# design.net
KiCad netlist of a schematic drawn in EasyEDA Pro
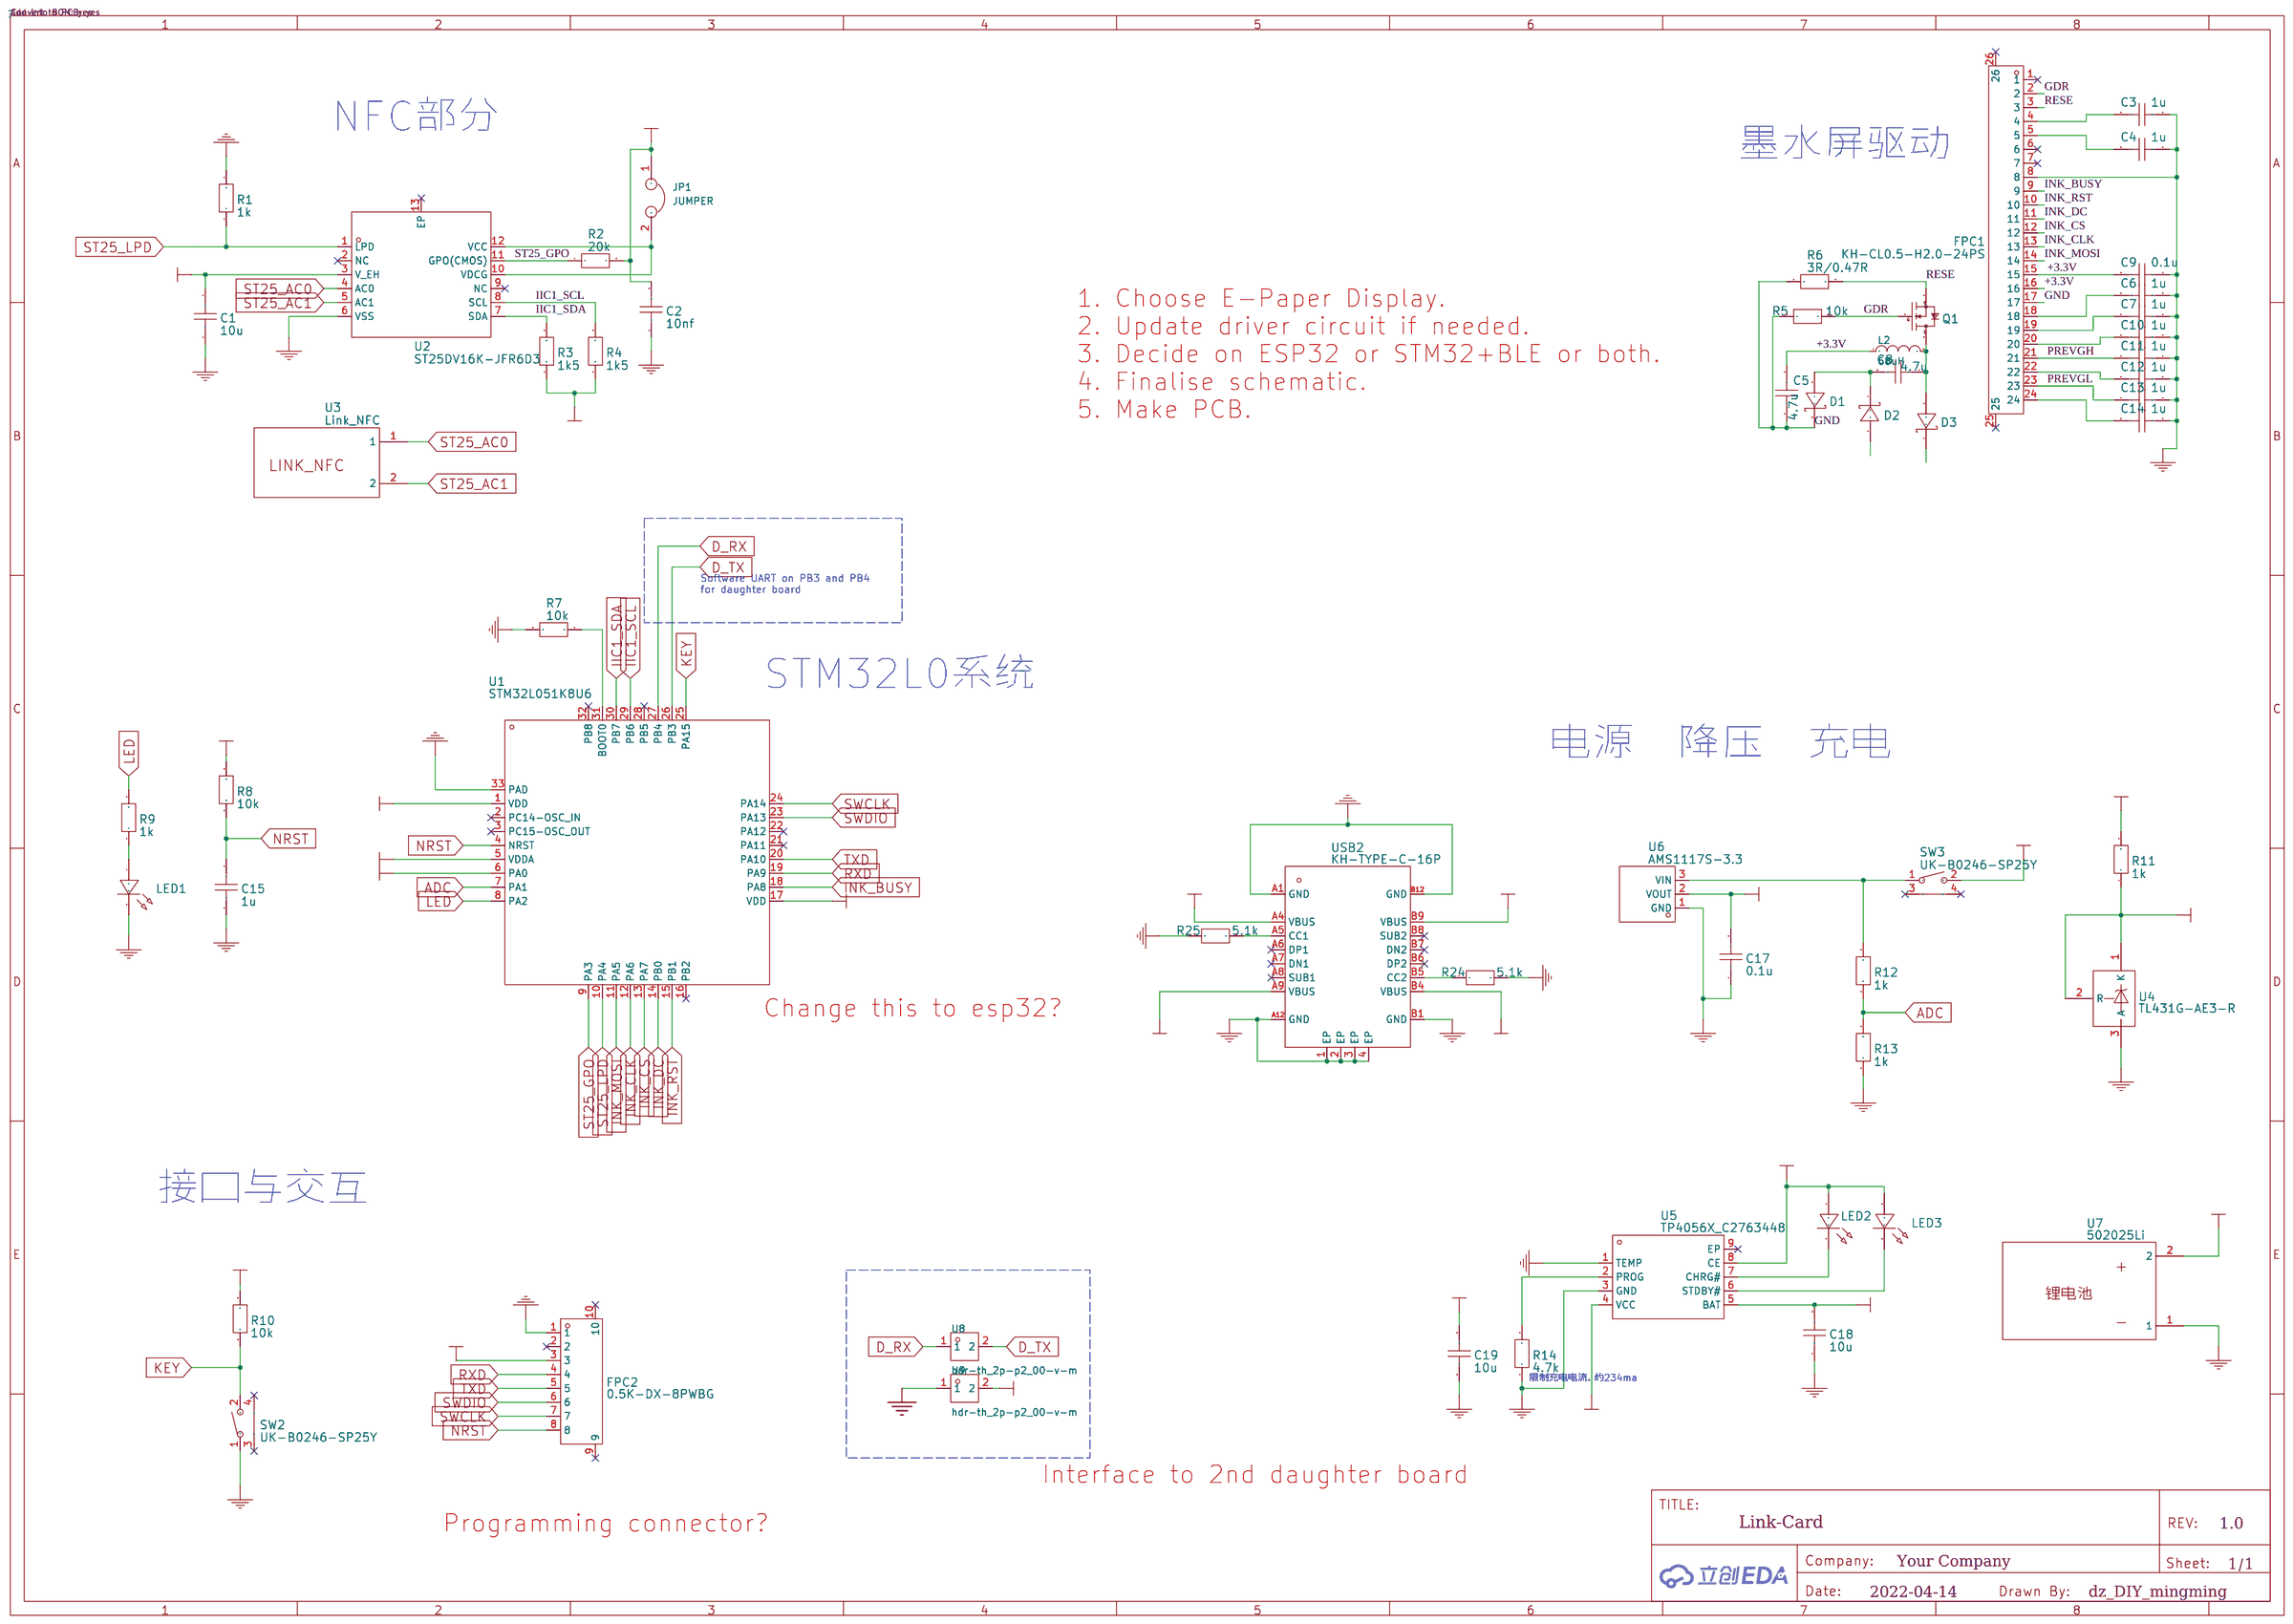
[diagram p0: schematic sheet]

(export (version "E")
  (design (tool "Eeschema 10.0.6"))
  (components
    (comp (ref "C1") (value "10u") (footprint "easyedapro:C0805") (libsource (lib "easyedapro") (part "10u")))
    (comp (ref "C2")
      (value "10nf")
      (footprint "easyedapro:C0603")
      (libsource (lib "easyedapro") (part "10nf"))
    )
    (comp (ref "C3") (value "1u") (footprint "easyedapro:C0603") (libsource (lib "easyedapro") (part "1u")))
    (comp (ref "C4") (value "1u") (footprint "easyedapro:C0603") (libsource (lib "easyedapro") (part "1u")))
    (comp (ref "C5")
      (value "4.7u")
      (footprint "easyedapro:C0603")
      (libsource (lib "easyedapro") (part "4.7u"))
    )
    (comp (ref "C6") (value "1u") (footprint "easyedapro:C0603") (libsource (lib "easyedapro") (part "1u")))
    (comp (ref "C7") (value "1u") (footprint "easyedapro:C0603") (libsource (lib "easyedapro") (part "1u")))
    (comp (ref "C8")
      (value "4.7u")
      (footprint "easyedapro:C0603")
      (libsource (lib "easyedapro") (part "4.7u"))
    )
    (comp (ref "C9")
      (value "0.1u")
      (footprint "easyedapro:C0603")
      (libsource (lib "easyedapro") (part "0.1u"))
    )
    (comp (ref "C10") (value "1u") (footprint "easyedapro:C0603") (libsource (lib "easyedapro") (part "1u")))
    (comp (ref "C11") (value "1u") (footprint "easyedapro:C0603") (libsource (lib "easyedapro") (part "1u")))
    (comp (ref "C12") (value "1u") (footprint "easyedapro:C0603") (libsource (lib "easyedapro") (part "1u")))
    (comp (ref "C13") (value "1u") (footprint "easyedapro:C0603") (libsource (lib "easyedapro") (part "1u")))
    (comp (ref "C14") (value "1u") (footprint "easyedapro:C0603") (libsource (lib "easyedapro") (part "1u")))
    (comp (ref "C15") (value "1u") (footprint "easyedapro:C0603") (libsource (lib "easyedapro") (part "1u")))
    (comp (ref "C17")
      (value "0.1u")
      (footprint "easyedapro:C0603")
      (libsource (lib "easyedapro") (part "0.1u"))
    )
    (comp (ref "C18")
      (value "10u")
      (footprint "easyedapro:C0805")
      (libsource (lib "easyedapro") (part "10u"))
    )
    (comp (ref "C19")
      (value "10u")
      (footprint "easyedapro:C0805")
      (libsource (lib "easyedapro") (part "10u"))
    )
    (comp (ref "D1")
      (value "MBR0530")
      (footprint "easyedapro:SOD-123F_L2.7-W1.7-LS3.7-RD-1")
      (libsource (lib "easyedapro") (part "MBR0530"))
    )
    (comp (ref "D2")
      (value "MBR0530")
      (footprint "easyedapro:SOD-123F_L2.7-W1.7-LS3.7-RD-1")
      (libsource (lib "easyedapro") (part "MBR0530"))
    )
    (comp (ref "D3")
      (value "MBR0530")
      (footprint "easyedapro:SOD-123F_L2.7-W1.7-LS3.7-RD-1")
      (libsource (lib "easyedapro") (part "MBR0530"))
    )
    (comp (ref "FPC1")
      (value "KH-CL0.5-H2.0-24PS")
      (footprint "easyedapro:FPC-SMD_24P-P0.50_KINGHELM_KH-CL0.5-H2.0-24PS")
      (fields (field (name "Manufacturer") "kinghelm(金航标)"))
      (libsource (lib "easyedapro") (part "KH-CL0.5-H2.0-24PS"))
    )
    (comp (ref "FPC2")
      (value "0.5K-DX-8PWBG")
      (footprint "easyedapro:FPC-SMD_8P-P0.50_HDGC_0.5K-DX-8PWBG")
      (fields (field (name "Manufacturer") "HDGC(华德共创)"))
      (libsource (lib "easyedapro") (part "0.5K-DX-8PWBG"))
    )
    (comp (ref "JP1")
      (value "JUMPER")
      (footprint "easyedapro:JUMPER-0603")
      (libsource (lib "easyedapro") (part "JUMPER"))
    )
    (comp (ref "L2")
      (value "68uH")
      (footprint "easyedapro:IND-SMD_L5.8-W5.2")
      (description "电感值:68uH;精度:±10%;额定电流:600mA;饱和电流(Isat):-;直流电阻(DCR):390mΩ;")
      (fields (field (name "Manufacturer Part") "CY54-68UH") (field (name "Manufacturer") "SHOU HAN(首韩)"))
      (libsource (lib "easyedapro") (part "CY54-68UH"))
    )
    (comp (ref "LED1")
      (value "LED-0805_B")
      (footprint "easyedapro:LED0805_BLUE")
      (fields (field (name "Manufacturer Part") "D-B080508B1-KS2") (field (name "Manufacturer") "方舟 ARKLED"))
      (libsource (lib "easyedapro") (part "LED-0805_B"))
    )
    (comp (ref "LED2")
      (value "LED-0805_R")
      (footprint "easyedapro:LED0805_RED")
      (fields
        (field (name "Manufacturer Part") "17-21SURC/S530-A3/TR8")
        (field (name "Manufacturer") "EVERLIGHT(台湾亿光)")
      )
      (libsource (lib "easyedapro") (part "LED-0805_R"))
    )
    (comp (ref "LED3")
      (value "LED-0805_G")
      (footprint "easyedapro:LED0805_GREEN")
      (fields (field (name "Manufacturer Part") "NCD0805G1") (field (name "Manufacturer") "国星光电"))
      (libsource (lib "easyedapro") (part "LED-0805_G"))
    )
    (comp (ref "Q1")
      (value "MOSFET-N+SI1304BDL")
      (footprint "easyedapro:SOT-323-3_L2.0-W1.3-P1.30-LS2.1-BR")
      (fields (field (name "Manufacturer Part") "?"))
      (libsource (lib "easyedapro") (part "MOSFET-N+SI1304BDL"))
    )
    (comp (ref "R1") (value "1k") (footprint "easyedapro:R0603") (libsource (lib "easyedapro") (part "1k")))
    (comp (ref "R2") (value "20k") (footprint "easyedapro:R0603") (libsource (lib "easyedapro") (part "20k")))
    (comp (ref "R3") (value "1k5") (footprint "easyedapro:R0603") (libsource (lib "easyedapro") (part "1k5")))
    (comp (ref "R4") (value "1k5") (footprint "easyedapro:R0603") (libsource (lib "easyedapro") (part "1k5")))
    (comp (ref "R5") (value "10k") (footprint "easyedapro:R0603") (libsource (lib "easyedapro") (part "10k")))
    (comp (ref "R6")
      (value "3R/0.47R")
      (footprint "easyedapro:R0603")
      (libsource (lib "easyedapro") (part "3R/0.47R"))
    )
    (comp (ref "R7") (value "10k") (footprint "easyedapro:R0603") (libsource (lib "easyedapro") (part "10k")))
    (comp (ref "R8") (value "10k") (footprint "easyedapro:R0603") (libsource (lib "easyedapro") (part "10k")))
    (comp (ref "R9") (value "1k") (footprint "easyedapro:R0603") (libsource (lib "easyedapro") (part "1k")))
    (comp (ref "R10")
      (value "10k")
      (footprint "easyedapro:R0603")
      (libsource (lib "easyedapro") (part "10k"))
    )
    (comp (ref "R11") (value "1k") (footprint "easyedapro:R0603") (libsource (lib "easyedapro") (part "1k")))
    (comp (ref "R12") (value "1k") (footprint "easyedapro:R0603") (libsource (lib "easyedapro") (part "1k")))
    (comp (ref "R13") (value "1k") (footprint "easyedapro:R0603") (libsource (lib "easyedapro") (part "1k")))
    (comp (ref "R14")
      (value "4.7k")
      (footprint "easyedapro:R0603")
      (libsource (lib "easyedapro") (part "4.7k"))
    )
    (comp (ref "R24")
      (value "5.1k")
      (footprint "easyedapro:R0603")
      (libsource (lib "easyedapro") (part "5.1k"))
    )
    (comp (ref "R25")
      (value "5.1k")
      (footprint "easyedapro:R0603")
      (libsource (lib "easyedapro") (part "5.1k"))
    )
    (comp (ref "SW2")
      (value "UK-B0246-SP25Y")
      (footprint "easyedapro:SW-SMD_UK-B0246-SP25Y")
      (fields (field (name "Manufacturer") "USAKRO"))
      (libsource (lib "easyedapro") (part "UK-B0246-SP25Y"))
    )
    (comp (ref "SW3")
      (value "UK-B0246-SP25Y")
      (footprint "easyedapro:SW-SMD_UK-B0246-SP25Y")
      (fields (field (name "Manufacturer") "USAKRO"))
      (libsource (lib "easyedapro") (part "UK-B0246-SP25Y"))
    )
    (comp (ref "U1")
      (value "STM32L051K8U6")
      (footprint "easyedapro:UFQFPN-32_L5.0-W5.0-P0.50-BL-EP")
      (fields (field (name "Manufacturer") "STMicroelectronics"))
      (libsource (lib "easyedapro") (part "STM32L051K8U6"))
    )
    (comp (ref "U2")
      (value "ST25DV16K-JFR6D3")
      (footprint "easyedapro:DFN-12_L3.0-W3.0-P0.50-LS3.0-BL-EP")
      (libsource (lib "easyedapro") (part "ST25DV16K-JFR6D3"))
    )
    (comp (ref "U3")
      (value "Link_NFC")
      (footprint "easyedapro:LINK_NFC")
      (libsource (lib "easyedapro") (part "Link_NFC"))
    )
    (comp (ref "U4")
      (value "TL431G-AE3-R")
      (footprint "easyedapro:SOT-23-3_L2.9-W1.3-P1.90-LS2.4-TR")
      (fields (field (name "Manufacturer") "UTC"))
      (libsource (lib "easyedapro") (part "TL431G-AE3-R"))
    )
    (comp (ref "U5")
      (value "TP4056X_C2763448")
      (footprint "easyedapro:SOP-8_L4.9-W3.9-P1.27-LS6.0-TL-EP-1")
      (fields (field (name "Manufacturer Part") "TP4056X") (field (name "Manufacturer") "TOPPOWER(南京拓微)"))
      (libsource (lib "easyedapro") (part "TP4056X_C2763448"))
    )
    (comp (ref "U6")
      (value "AMS1117S-3.3")
      (footprint "easyedapro:SOT-89-3_L4.5-W2.5-P1.50-LS4.2-BR")
      (fields (field (name "Manufacturer") "JSMSEMI"))
      (libsource (lib "easyedapro") (part "AMS1117S-3.3"))
    )
    (comp (ref "U7")
      (value "502025Li")
      (footprint "easyedapro:502025LI")
      (libsource (lib "easyedapro") (part "502025Li"))
    )
    (comp (ref "U8")
      (value "hdr-th_2p-p2_00-v-m")
      (footprint "easyedapro:HDR-TH_2P-P2.00-V-M-1")
      (libsource (lib "easyedapro") (part "HDR-TH_2P-P2_00-V-M"))
    )
    (comp (ref "U9")
      (value "hdr-th_2p-p2_00-v-m")
      (footprint "easyedapro:HDR-TH_2P-P2.00-V-M-1")
      (libsource (lib "easyedapro") (part "HDR-TH_2P-P2_00-V-M"))
    )
    (comp (ref "USB2")
      (value "KH-TYPE-C-16P")
      (footprint "easyedapro:USB-C-SMD_KH-TYPE-C-16P")
      (fields (field (name "Manufacturer") "Shenzhen Kinghelm Elec"))
      (libsource (lib "easyedapro") (part "KH-TYPE-C-16P"))
    )
  )
  (nets
    (net (code "1") (name "+2.5V") (class "Default")
      (node (ref "R11") (pin "1") (pinfunction "1_1") (pintype "input"))
      (node (ref "U1") (pin "6") (pinfunction "PA0_6") (pintype "input"))
      (node (ref "U4") (pin "1") (pinfunction "K_1") (pintype "input"))
      (node (ref "U4") (pin "2") (pinfunction "R_2") (pintype "input"))
    )
    (net (code "2") (name "+3.3V") (class "Default")
      (node (ref "C1") (pin "2") (pinfunction "2_2") (pintype "input"))
      (node (ref "C17") (pin "2") (pinfunction "2_2") (pintype "input"))
      (node (ref "C2") (pin "2") (pinfunction "2_2") (pintype "input"))
      (node (ref "C5") (pin "2") (pinfunction "2_2") (pintype "input"))
      (node (ref "C9") (pin "1") (pinfunction "1_1") (pintype "input"))
      (node (ref "FPC1") (pin "15") (pinfunction "15_15") (pintype "input"))
      (node (ref "FPC1") (pin "16") (pinfunction "16_16") (pintype "input"))
      (node (ref "FPC2") (pin "3") (pinfunction "3_3") (pintype "input"))
      (node (ref "JP1") (pin "1") (pinfunction "1_1") (pintype "input"))
      (node (ref "L2") (pin "1") (pinfunction "1_1") (pintype "input"))
      (node (ref "R10") (pin "2") (pinfunction "2_2") (pintype "input"))
      (node (ref "R11") (pin "2") (pinfunction "2_2") (pintype "input"))
      (node (ref "R2") (pin "2") (pinfunction "2_2") (pintype "input"))
      (node (ref "R3") (pin "1") (pinfunction "1_1") (pintype "input"))
      (node (ref "R4") (pin "1") (pinfunction "1_1") (pintype "input"))
      (node (ref "R8") (pin "2") (pinfunction "2_2") (pintype "input"))
      (node (ref "U1") (pin "1") (pinfunction "VDD_1") (pintype "input"))
      (node (ref "U1") (pin "17") (pinfunction "VDD_17") (pintype "input"))
      (node (ref "U1") (pin "5") (pinfunction "VDDA_5") (pintype "input"))
      (node (ref "U2") (pin "3") (pinfunction "V_EH_3") (pintype "input"))
      (node (ref "U6") (pin "2") (pinfunction "VOUT_2") (pintype "input"))
    )
    (net (code "3") (name "+5V") (class "Default")
      (node (ref "C19") (pin "2") (pinfunction "2_2") (pintype "input"))
      (node (ref "LED2") (pin "1") (pinfunction "1_1") (pintype "input"))
      (node (ref "LED3") (pin "1") (pinfunction "1_1") (pintype "input"))
      (node (ref "U5") (pin "4") (pinfunction "VCC_4") (pintype "input"))
      (node (ref "U5") (pin "8") (pinfunction "CE_8") (pintype "input"))
      (node (ref "USB2") (pin "A4") (pinfunction "VBUS_A4") (pintype "input"))
      (node (ref "USB2") (pin "A9") (pinfunction "VBUS_A9") (pintype "input"))
      (node (ref "USB2") (pin "B4") (pinfunction "VBUS_B4") (pintype "input"))
      (node (ref "USB2") (pin "B9") (pinfunction "VBUS_B9") (pintype "input"))
    )
    (net (code "4") (name "/GDR") (class "Default")
      (node (ref "FPC1") (pin "2") (pinfunction "2_2") (pintype "input"))
      (node (ref "Q1") (pin "1") (pinfunction "G_1") (pintype "input"))
      (node (ref "R5") (pin "2") (pinfunction "2_2") (pintype "input"))
    )
    (net (code "5") (name "/PREVGH") (class "Default")
      (node (ref "C11") (pin "1") (pinfunction "1_1") (pintype "input"))
      (node (ref "FPC1") (pin "21") (pinfunction "21_21") (pintype "input"))
    )
    (net (code "6") (name "/PREVGL") (class "Default")
      (node (ref "C13") (pin "1") (pinfunction "1_1") (pintype "input"))
      (node (ref "FPC1") (pin "23") (pinfunction "23_23") (pintype "input"))
    )
    (net (code "7") (name "/RESE") (class "Default")
      (node (ref "FPC1") (pin "3") (pinfunction "3_3") (pintype "input"))
      (node (ref "Q1") (pin "2") (pinfunction "S_2") (pintype "input"))
      (node (ref "R6") (pin "2") (pinfunction "2_2") (pintype "input"))
    )
    (net (code "8") (name "ADC") (class "Default")
      (node (ref "R12") (pin "1") (pinfunction "1_1") (pintype "input"))
      (node (ref "R13") (pin "2") (pinfunction "2_2") (pintype "input"))
      (node (ref "U1") (pin "7") (pinfunction "PA1_7") (pintype "input"))
    )
    (net (code "9") (name "D_RX") (class "Default")
      (node (ref "U1") (pin "27") (pinfunction "PB4_27") (pintype "input"))
      (node (ref "U8") (pin "1") (pinfunction "1_1") (pintype "input"))
    )
    (net (code "10") (name "D_TX") (class "Default")
      (node (ref "U1") (pin "26") (pinfunction "PB3_26") (pintype "input"))
      (node (ref "U8") (pin "2") (pinfunction "2_2") (pintype "input"))
    )
    (net (code "11") (name "GND") (class "Default")
      (node (ref "C1") (pin "1") (pinfunction "1_1") (pintype "input"))
      (node (ref "C10") (pin "2") (pinfunction "2_2") (pintype "input"))
      (node (ref "C11") (pin "2") (pinfunction "2_2") (pintype "input"))
      (node (ref "C12") (pin "2") (pinfunction "2_2") (pintype "input"))
      (node (ref "C13") (pin "2") (pinfunction "2_2") (pintype "input"))
      (node (ref "C14") (pin "2") (pinfunction "2_2") (pintype "input"))
      (node (ref "C15") (pin "1") (pinfunction "1_1") (pintype "input"))
      (node (ref "C17") (pin "1") (pinfunction "1_1") (pintype "input"))
      (node (ref "C18") (pin "1") (pinfunction "1_1") (pintype "input"))
      (node (ref "C19") (pin "1") (pinfunction "1_1") (pintype "input"))
      (node (ref "C2") (pin "1") (pinfunction "1_1") (pintype "input"))
      (node (ref "C3") (pin "2") (pinfunction "2_2") (pintype "input"))
      (node (ref "C4") (pin "2") (pinfunction "2_2") (pintype "input"))
      (node (ref "C5") (pin "1") (pinfunction "1_1") (pintype "input"))
      (node (ref "C6") (pin "2") (pinfunction "2_2") (pintype "input"))
      (node (ref "C7") (pin "2") (pinfunction "2_2") (pintype "input"))
      (node (ref "C9") (pin "2") (pinfunction "2_2") (pintype "input"))
      (node (ref "D1") (pin "1") (pinfunction "K_1") (pintype "input"))
      (node (ref "FPC1") (pin "17") (pinfunction "17_17") (pintype "input"))
      (node (ref "FPC1") (pin "8") (pinfunction "8_8") (pintype "input"))
      (node (ref "FPC2") (pin "1") (pinfunction "1_1") (pintype "input"))
      (node (ref "LED1") (pin "2") (pinfunction "2_2") (pintype "input"))
      (node (ref "R1") (pin "2") (pinfunction "2_2") (pintype "input"))
      (node (ref "R13") (pin "1") (pinfunction "1_1") (pintype "input"))
      (node (ref "R14") (pin "1") (pinfunction "1_1") (pintype "input"))
      (node (ref "R24") (pin "2") (pinfunction "2_2") (pintype "input"))
      (node (ref "R25") (pin "1") (pinfunction "1_1") (pintype "input"))
      (node (ref "R5") (pin "1") (pinfunction "1_1") (pintype "input"))
      (node (ref "R6") (pin "1") (pinfunction "1_1") (pintype "input"))
      (node (ref "R7") (pin "2") (pinfunction "2_2") (pintype "input"))
      (node (ref "SW2") (pin "1") (pinfunction "1_1") (pintype "input"))
      (node (ref "U1") (pin "33") (pinfunction "PAD_33") (pintype "input"))
      (node (ref "U2") (pin "6") (pinfunction "VSS_6") (pintype "input"))
      (node (ref "U4") (pin "3") (pinfunction "A_3") (pintype "input"))
      (node (ref "U5") (pin "1") (pinfunction "TEMP_1") (pintype "input"))
      (node (ref "U5") (pin "3") (pinfunction "GND_3") (pintype "input"))
      (node (ref "U6") (pin "1") (pinfunction "GND_1") (pintype "input"))
      (node (ref "U7") (pin "1") (pinfunction "1_1") (pintype "input"))
      (node (ref "U9") (pin "1") (pinfunction "1_1") (pintype "input"))
      (node (ref "USB2") (pin "1") (pinfunction "EP_1") (pintype "input"))
      (node (ref "USB2") (pin "2") (pinfunction "EP_2") (pintype "input"))
      (node (ref "USB2") (pin "3") (pinfunction "EP_3") (pintype "input"))
      (node (ref "USB2") (pin "4") (pinfunction "EP_4") (pintype "input"))
      (node (ref "USB2") (pin "A1") (pinfunction "GND_A1") (pintype "input"))
      (node (ref "USB2") (pin "A12") (pinfunction "GND_A12") (pintype "input"))
      (node (ref "USB2") (pin "B1") (pinfunction "GND_B1") (pintype "input"))
      (node (ref "USB2") (pin "B12") (pinfunction "GND_B12") (pintype "input"))
    )
    (net (code "12") (name "IIC1_SCL") (class "Default")
      (node (ref "R4") (pin "2") (pinfunction "2_2") (pintype "input"))
      (node (ref "U1") (pin "29") (pinfunction "PB6_29") (pintype "input"))
      (node (ref "U2") (pin "8") (pinfunction "SCL_8") (pintype "input"))
    )
    (net (code "13") (name "IIC1_SDA") (class "Default")
      (node (ref "R3") (pin "2") (pinfunction "2_2") (pintype "input"))
      (node (ref "U1") (pin "30") (pinfunction "PB7_30") (pintype "input"))
      (node (ref "U2") (pin "7") (pinfunction "SDA_7") (pintype "input"))
    )
    (net (code "14") (name "INK_BUSY") (class "Default")
      (node (ref "FPC1") (pin "9") (pinfunction "9_9") (pintype "input"))
      (node (ref "U1") (pin "18") (pinfunction "PA8_18") (pintype "input"))
    )
    (net (code "15") (name "INK_CLK") (class "Default")
      (node (ref "FPC1") (pin "13") (pinfunction "13_13") (pintype "input"))
      (node (ref "U1") (pin "12") (pinfunction "PA6_12") (pintype "input"))
    )
    (net (code "16") (name "INK_CS") (class "Default")
      (node (ref "FPC1") (pin "12") (pinfunction "12_12") (pintype "input"))
      (node (ref "U1") (pin "13") (pinfunction "PA7_13") (pintype "input"))
    )
    (net (code "17") (name "INK_DC") (class "Default")
      (node (ref "FPC1") (pin "11") (pinfunction "11_11") (pintype "input"))
      (node (ref "U1") (pin "14") (pinfunction "PB0_14") (pintype "input"))
    )
    (net (code "18") (name "INK_MOSI") (class "Default")
      (node (ref "FPC1") (pin "14") (pinfunction "14_14") (pintype "input"))
      (node (ref "U1") (pin "11") (pinfunction "PA5_11") (pintype "input"))
    )
    (net (code "19") (name "INK_RST") (class "Default")
      (node (ref "FPC1") (pin "10") (pinfunction "10_10") (pintype "input"))
      (node (ref "U1") (pin "15") (pinfunction "PB1_15") (pintype "input"))
    )
    (net (code "20") (name "KEY") (class "Default")
      (node (ref "R10") (pin "1") (pinfunction "1_1") (pintype "input"))
      (node (ref "SW2") (pin "2") (pinfunction "2_2") (pintype "input"))
      (node (ref "U1") (pin "25") (pinfunction "PA15_25") (pintype "input"))
    )
    (net (code "21") (name "LED") (class "Default")
      (node (ref "R9") (pin "2") (pinfunction "2_2") (pintype "input"))
      (node (ref "U1") (pin "8") (pinfunction "PA2_8") (pintype "input"))
    )
    (net (code "22") (name "NRST") (class "Default")
      (node (ref "C15") (pin "2") (pinfunction "2_2") (pintype "input"))
      (node (ref "FPC2") (pin "8") (pinfunction "8_8") (pintype "input"))
      (node (ref "R8") (pin "1") (pinfunction "1_1") (pintype "input"))
      (node (ref "U1") (pin "4") (pinfunction "NRST_4") (pintype "input"))
    )
    (net (code "23") (name "Net-(C3-Pad1)") (class "Default")
      (node (ref "C3") (pin "1") (pinfunction "1_1") (pintype "input"))
      (node (ref "FPC1") (pin "4") (pinfunction "4_4") (pintype "input"))
    )
    (net (code "24") (name "Net-(C4-Pad1)") (class "Default")
      (node (ref "C4") (pin "1") (pinfunction "1_1") (pintype "input"))
      (node (ref "FPC1") (pin "5") (pinfunction "5_5") (pintype "input"))
    )
    (net (code "25") (name "Net-(C6-Pad1)") (class "Default")
      (node (ref "C6") (pin "1") (pinfunction "1_1") (pintype "input"))
      (node (ref "FPC1") (pin "18") (pinfunction "18_18") (pintype "input"))
    )
    (net (code "26") (name "Net-(C7-Pad1)") (class "Default")
      (node (ref "C7") (pin "1") (pinfunction "1_1") (pintype "input"))
      (node (ref "FPC1") (pin "19") (pinfunction "19_19") (pintype "input"))
    )
    (net (code "27") (name "Net-(C10-Pad1)") (class "Default")
      (node (ref "C10") (pin "1") (pinfunction "1_1") (pintype "input"))
      (node (ref "FPC1") (pin "20") (pinfunction "20_20") (pintype "input"))
    )
    (net (code "28") (name "Net-(C12-Pad1)") (class "Default")
      (node (ref "C12") (pin "1") (pinfunction "1_1") (pintype "input"))
      (node (ref "FPC1") (pin "22") (pinfunction "22_22") (pintype "input"))
    )
    (net (code "29") (name "Net-(C14-Pad1)") (class "Default")
      (node (ref "C14") (pin "1") (pinfunction "1_1") (pintype "input"))
      (node (ref "FPC1") (pin "24") (pinfunction "24_24") (pintype "input"))
    )
    (net (code "30") (name "Net-(D1-A)") (class "Default")
      (node (ref "C8") (pin "2") (pinfunction "2_2") (pintype "input"))
      (node (ref "D1") (pin "2") (pinfunction "A_2") (pintype "input"))
      (node (ref "D2") (pin "1") (pinfunction "K_1") (pintype "input"))
    )
    (net (code "31") (name "Net-(D3-A)") (class "Default")
      (node (ref "C8") (pin "1") (pinfunction "1_1") (pintype "input"))
      (node (ref "D3") (pin "2") (pinfunction "A_2") (pintype "input"))
      (node (ref "L2") (pin "2") (pinfunction "2_2") (pintype "input"))
      (node (ref "Q1") (pin "3") (pinfunction "D_3") (pintype "input"))
    )
    (net (code "32") (name "Net-(LED1-Pad1)") (class "Default")
      (node (ref "LED1") (pin "1") (pinfunction "1_1") (pintype "input"))
      (node (ref "R9") (pin "1") (pinfunction "1_1") (pintype "input"))
    )
    (net (code "33") (name "Net-(U1-BOOT0)") (class "Default")
      (node (ref "R7") (pin "1") (pinfunction "1_1") (pintype "input"))
      (node (ref "U1") (pin "31") (pinfunction "BOOT0_31") (pintype "input"))
    )
    (net (code "34") (name "Net-(U2-VCC)") (class "Default")
      (node (ref "JP1") (pin "2") (pinfunction "2_2") (pintype "input"))
      (node (ref "U2") (pin "10") (pinfunction "VDCG_10") (pintype "input"))
      (node (ref "U2") (pin "12") (pinfunction "VCC_12") (pintype "input"))
    )
    (net (code "35") (name "Net-(U5-CHRG#)") (class "Default")
      (node (ref "LED2") (pin "2") (pinfunction "2_2") (pintype "input"))
      (node (ref "U5") (pin "7") (pinfunction "CHRG#_7") (pintype "input"))
    )
    (net (code "36") (name "Net-(U5-PROG)") (class "Default")
      (node (ref "R14") (pin "2") (pinfunction "2_2") (pintype "input"))
      (node (ref "U5") (pin "2") (pinfunction "PROG_2") (pintype "input"))
    )
    (net (code "37") (name "Net-(U5-STDBY#)") (class "Default")
      (node (ref "LED3") (pin "2") (pinfunction "2_2") (pintype "input"))
      (node (ref "U5") (pin "6") (pinfunction "STDBY#_6") (pintype "input"))
    )
    (net (code "38") (name "Net-(U6-VIN)") (class "Default")
      (node (ref "R12") (pin "2") (pinfunction "2_2") (pintype "input"))
      (node (ref "SW3") (pin "1") (pinfunction "1_1") (pintype "input"))
      (node (ref "U6") (pin "3") (pinfunction "VIN_3") (pintype "input"))
    )
    (net (code "39") (name "Net-(USB2-CC1)") (class "Default")
      (node (ref "R25") (pin "2") (pinfunction "2_2") (pintype "input"))
      (node (ref "USB2") (pin "A5") (pinfunction "CC1_A5") (pintype "input"))
    )
    (net (code "40") (name "Net-(USB2-CC2)") (class "Default")
      (node (ref "R24") (pin "1") (pinfunction "1_1") (pintype "input"))
      (node (ref "USB2") (pin "B5") (pinfunction "CC2_B5") (pintype "input"))
    )
    (net (code "41") (name "RXD") (class "Default")
      (node (ref "FPC2") (pin "4") (pinfunction "4_4") (pintype "input"))
      (node (ref "U1") (pin "19") (pinfunction "PA9_19") (pintype "input"))
    )
    (net (code "42") (name "ST25_AC0") (class "Default")
      (node (ref "U2") (pin "4") (pinfunction "AC0_4") (pintype "input"))
      (node (ref "U3") (pin "1") (pinfunction "1_1") (pintype "input"))
    )
    (net (code "43") (name "ST25_AC1") (class "Default")
      (node (ref "U2") (pin "5") (pinfunction "AC1_5") (pintype "input"))
      (node (ref "U3") (pin "2") (pinfunction "2_2") (pintype "input"))
    )
    (net (code "44") (name "ST25_GPO") (class "Default")
      (node (ref "R2") (pin "1") (pinfunction "1_1") (pintype "input"))
      (node (ref "U1") (pin "9") (pinfunction "PA3_9") (pintype "input"))
      (node (ref "U2") (pin "11") (pinfunction "GPO(CMOS)_11") (pintype "input"))
    )
    (net (code "45") (name "ST25_LPD") (class "Default")
      (node (ref "R1") (pin "1") (pinfunction "1_1") (pintype "input"))
      (node (ref "U1") (pin "10") (pinfunction "PA4_10") (pintype "input"))
      (node (ref "U2") (pin "1") (pinfunction "LPD_1") (pintype "input"))
    )
    (net (code "46") (name "SWCLK") (class "Default")
      (node (ref "FPC2") (pin "7") (pinfunction "7_7") (pintype "input"))
      (node (ref "U1") (pin "24") (pinfunction "PA14_24") (pintype "input"))
    )
    (net (code "47") (name "SWDIO") (class "Default")
      (node (ref "FPC2") (pin "6") (pinfunction "6_6") (pintype "input"))
      (node (ref "U1") (pin "23") (pinfunction "PA13_23") (pintype "input"))
    )
    (net (code "48") (name "TXD") (class "Default")
      (node (ref "FPC2") (pin "5") (pinfunction "5_5") (pintype "input"))
      (node (ref "U1") (pin "20") (pinfunction "PA10_20") (pintype "input"))
    )
    (net (code "49") (name "VBAT") (class "Default")
      (node (ref "C18") (pin "2") (pinfunction "2_2") (pintype "input"))
      (node (ref "SW3") (pin "2") (pinfunction "2_2") (pintype "input"))
      (node (ref "U5") (pin "5") (pinfunction "BAT_5") (pintype "input"))
      (node (ref "U7") (pin "2") (pinfunction "2_2") (pintype "input"))
      (node (ref "U9") (pin "2") (pinfunction "2_2") (pintype "input"))
    )
    (net (code "50") (name "unconnected-(D2-A-Pad2)") (class "Default")
      (node (ref "D2") (pin "2") (pinfunction "A_2") (pintype "input"))
    )
    (net (code "51") (name "unconnected-(D3-K-Pad1)") (class "Default")
      (node (ref "D3") (pin "1") (pinfunction "K_1") (pintype "input"))
    )
    (net (code "52") (name "unconnected-(FPC1-Pad1)") (class "Default")
      (node (ref "FPC1") (pin "1") (pinfunction "1_1") (pintype "input+no_connect"))
    )
    (net (code "53") (name "unconnected-(FPC1-Pad6)") (class "Default")
      (node (ref "FPC1") (pin "6") (pinfunction "6_6") (pintype "input+no_connect"))
    )
    (net (code "54") (name "unconnected-(FPC1-Pad7)") (class "Default")
      (node (ref "FPC1") (pin "7") (pinfunction "7_7") (pintype "input+no_connect"))
    )
    (net (code "55") (name "unconnected-(FPC1-Pad25)") (class "Default")
      (node (ref "FPC1") (pin "25") (pinfunction "25_25") (pintype "input+no_connect"))
    )
    (net (code "56") (name "unconnected-(FPC1-Pad26)") (class "Default")
      (node (ref "FPC1") (pin "26") (pinfunction "26_26") (pintype "input+no_connect"))
    )
    (net (code "57") (name "unconnected-(FPC2-Pad2)") (class "Default")
      (node (ref "FPC2") (pin "2") (pinfunction "2_2") (pintype "input+no_connect"))
    )
    (net (code "58") (name "unconnected-(FPC2-Pad9)") (class "Default")
      (node (ref "FPC2") (pin "9") (pinfunction "9_9") (pintype "input+no_connect"))
    )
    (net (code "59") (name "unconnected-(FPC2-Pad10)") (class "Default")
      (node (ref "FPC2") (pin "10") (pinfunction "10_10") (pintype "input+no_connect"))
    )
    (net (code "60") (name "unconnected-(SW2-EP-Pad3)") (class "Default")
      (node (ref "SW2") (pin "3") (pinfunction "EP_3") (pintype "input+no_connect"))
    )
    (net (code "61") (name "unconnected-(SW2-EP-Pad4)") (class "Default")
      (node (ref "SW2") (pin "4") (pinfunction "EP_4") (pintype "input+no_connect"))
    )
    (net (code "62") (name "unconnected-(SW3-EP-Pad3)") (class "Default")
      (node (ref "SW3") (pin "3") (pinfunction "EP_3") (pintype "input+no_connect"))
    )
    (net (code "63") (name "unconnected-(SW3-EP-Pad4)") (class "Default")
      (node (ref "SW3") (pin "4") (pinfunction "EP_4") (pintype "input+no_connect"))
    )
    (net (code "64") (name "unconnected-(U1-PA11-Pad21)") (class "Default")
      (node (ref "U1") (pin "21") (pinfunction "PA11_21") (pintype "input+no_connect"))
    )
    (net (code "65") (name "unconnected-(U1-PA12-Pad22)") (class "Default")
      (node (ref "U1") (pin "22") (pinfunction "PA12_22") (pintype "input+no_connect"))
    )
    (net (code "66") (name "unconnected-(U1-PB2-Pad16)") (class "Default")
      (node (ref "U1") (pin "16") (pinfunction "PB2_16") (pintype "input+no_connect"))
    )
    (net (code "67") (name "unconnected-(U1-PB5-Pad28)") (class "Default")
      (node (ref "U1") (pin "28") (pinfunction "PB5_28") (pintype "input+no_connect"))
    )
    (net (code "68") (name "unconnected-(U1-PB8-Pad32)") (class "Default")
      (node (ref "U1") (pin "32") (pinfunction "PB8_32") (pintype "input+no_connect"))
    )
    (net (code "69") (name "unconnected-(U1-PC14-OSC_IN-Pad2)") (class "Default")
      (node (ref "U1") (pin "2") (pinfunction "PC14-OSC_IN_2") (pintype "input+no_connect"))
    )
    (net (code "70") (name "unconnected-(U1-PC15-OSC_OUT-Pad3)") (class "Default")
      (node (ref "U1") (pin "3") (pinfunction "PC15-OSC_OUT_3") (pintype "input+no_connect"))
    )
    (net (code "71") (name "unconnected-(U2-EP-Pad13)") (class "Default")
      (node (ref "U2") (pin "13") (pinfunction "EP_13") (pintype "input+no_connect"))
    )
    (net (code "72") (name "unconnected-(U2-NC-Pad2)") (class "Default")
      (node (ref "U2") (pin "2") (pinfunction "NC_2") (pintype "input+no_connect"))
    )
    (net (code "73") (name "unconnected-(U2-NC-Pad9)") (class "Default")
      (node (ref "U2") (pin "9") (pinfunction "NC_9") (pintype "input+no_connect"))
    )
    (net (code "74") (name "unconnected-(U5-EP-Pad9)") (class "Default")
      (node (ref "U5") (pin "9") (pinfunction "EP_9") (pintype "input+no_connect"))
    )
    (net (code "75") (name "unconnected-(USB2-DN1-PadA7)") (class "Default")
      (node (ref "USB2") (pin "A7") (pinfunction "DN1_A7") (pintype "input+no_connect"))
    )
    (net (code "76") (name "unconnected-(USB2-DN2-PadB7)") (class "Default")
      (node (ref "USB2") (pin "B7") (pinfunction "DN2_B7") (pintype "input+no_connect"))
    )
    (net (code "77") (name "unconnected-(USB2-DP1-PadA6)") (class "Default")
      (node (ref "USB2") (pin "A6") (pinfunction "DP1_A6") (pintype "input+no_connect"))
    )
    (net (code "78") (name "unconnected-(USB2-DP2-PadB6)") (class "Default")
      (node (ref "USB2") (pin "B6") (pinfunction "DP2_B6") (pintype "input+no_connect"))
    )
    (net (code "79") (name "unconnected-(USB2-SUB1-PadA8)") (class "Default")
      (node (ref "USB2") (pin "A8") (pinfunction "SUB1_A8") (pintype "input+no_connect"))
    )
    (net (code "80") (name "unconnected-(USB2-SUB2-PadB8)") (class "Default")
      (node (ref "USB2") (pin "B8") (pinfunction "SUB2_B8") (pintype "input+no_connect"))
    )
  )
)
